# 02_Interfaces.net
KiCad netlist of a schematic drawn in Altium Designer
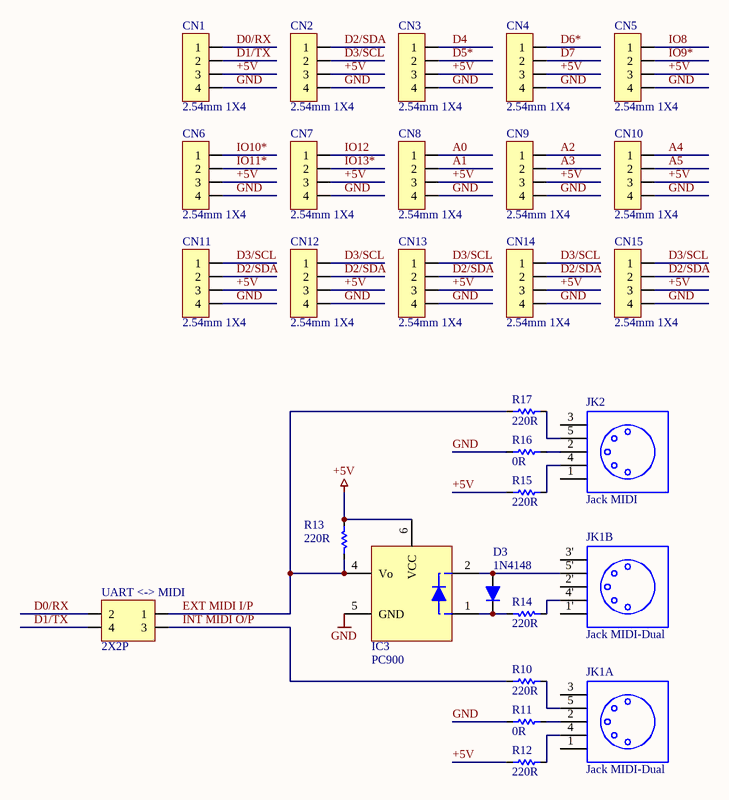
[diagram p0: 02.Interfaces.SchDoc]

(export (version "E")
  (design (tool "Eeschema 10.0.6"))
  (components
    (comp (ref "CN1")
      (value "2.54mm 1X4")
      (footprint "Grove-4P-180D")
      (libsource (lib "MainnoLab library") (part "Connector 1X4"))
    )
    (comp (ref "CN2")
      (value "2.54mm 1X4")
      (footprint "Grove-4P-180D")
      (libsource (lib "MainnoLab library") (part "Connector 1X4"))
    )
    (comp (ref "CN3")
      (value "2.54mm 1X4")
      (footprint "Grove-4P-180D")
      (libsource (lib "MainnoLab library") (part "Connector 1X4"))
    )
    (comp (ref "CN4")
      (value "2.54mm 1X4")
      (footprint "Grove-4P-180D")
      (libsource (lib "MainnoLab library") (part "Connector 1X4"))
    )
    (comp (ref "CN5")
      (value "2.54mm 1X4")
      (footprint "Grove-4P-180D")
      (libsource (lib "MainnoLab library") (part "Connector 1X4"))
    )
    (comp (ref "CN6")
      (value "2.54mm 1X4")
      (footprint "Grove-4P-180D")
      (libsource (lib "MainnoLab library") (part "Connector 1X4"))
    )
    (comp (ref "CN7")
      (value "2.54mm 1X4")
      (footprint "Grove-4P-180D")
      (libsource (lib "MainnoLab library") (part "Connector 1X4"))
    )
    (comp (ref "CN8")
      (value "2.54mm 1X4")
      (footprint "Grove-4P-180D")
      (libsource (lib "MainnoLab library") (part "Connector 1X4"))
    )
    (comp (ref "CN9")
      (value "2.54mm 1X4")
      (footprint "Grove-4P-180D")
      (libsource (lib "MainnoLab library") (part "Connector 1X4"))
    )
    (comp (ref "CN10")
      (value "2.54mm 1X4")
      (footprint "Grove-4P-180D")
      (libsource (lib "MainnoLab library") (part "Connector 1X4"))
    )
    (comp (ref "CN11")
      (value "2.54mm 1X4")
      (footprint "Grove-4P-180D")
      (libsource (lib "MainnoLab library") (part "Connector 1X4"))
    )
    (comp (ref "CN12")
      (value "2.54mm 1X4")
      (footprint "Grove-4P-180D")
      (libsource (lib "MainnoLab library") (part "Connector 1X4"))
    )
    (comp (ref "CN13")
      (value "2.54mm 1X4")
      (footprint "Grove-4P-180D")
      (libsource (lib "MainnoLab library") (part "Connector 1X4"))
    )
    (comp (ref "CN14")
      (value "2.54mm 1X4")
      (footprint "Grove-4P-180D")
      (libsource (lib "MainnoLab library") (part "Connector 1X4"))
    )
    (comp (ref "CN15")
      (value "2.54mm 1X4")
      (footprint "Grove-4P-180D")
      (libsource (lib "MainnoLab library") (part "Connector 1X4"))
    )
    (comp (ref "D3")
      (value "1N4148")
      (footprint "SOD-323")
      (libsource (lib "Jixuan's library") (part "Diode 1N4148"))
    )
    (comp (ref "IC3")
      (value "PC900")
      (footprint "DIP-6")
      (description "Sharp PC900 Optoisolator")
      (libsource (lib "Jixuan's library") (part "Optoisolator PC900"))
    )
    (comp (ref "JK1")
      (value "Jack MIDI-Dual")
      (footprint "HDC-052")
      (description "Dual MIDI Connector")
      (libsource (lib "Jixuan's library") (part "Jack MIDI-Dual"))
    )
    (comp (ref "JK2")
      (value "Jack MIDI")
      (footprint "HDC-052-01")
      (libsource (lib "MainnoLab library") (part "Jack MIDI"))
    )
    (comp (ref "R10")
      (value "220R")
      (footprint "R0603-ROUND")
      (libsource (lib "Jixuan's library") (part "Resistor"))
    )
    (comp (ref "R11")
      (value "0R")
      (footprint "R0603-ROUND")
      (libsource (lib "Jixuan's library") (part "Resistor"))
    )
    (comp (ref "R12")
      (value "220R")
      (footprint "R0603-ROUND")
      (libsource (lib "Jixuan's library") (part "Resistor"))
    )
    (comp (ref "R13")
      (value "220R")
      (footprint "R0603-ROUND")
      (libsource (lib "Jixuan's library") (part "Resistor"))
    )
    (comp (ref "R14")
      (value "220R")
      (footprint "R0603-ROUND")
      (libsource (lib "Jixuan's library") (part "Resistor"))
    )
    (comp (ref "R15")
      (value "220R")
      (footprint "R0603-ROUND")
      (libsource (lib "Jixuan's library") (part "Resistor"))
    )
    (comp (ref "R16")
      (value "0R")
      (footprint "R0603-ROUND")
      (libsource (lib "Jixuan's library") (part "Resistor"))
    )
    (comp (ref "R17")
      (value "220R")
      (footprint "R0603-ROUND")
      (libsource (lib "Jixuan's library") (part "Resistor"))
    )
    (comp (ref "UART <-> MIDI")
      (value "2X2P")
      (footprint "A2541WV0-2X2P")
      (libsource (lib "Jixuan's library") (part "Connector 2X2"))
    )
  )
  (nets
    (net (code "1") (name "+5V") (class "Default")
      (node (ref "CN1") (pin "3") (pinfunction "3_3") (pintype "passive"))
      (node (ref "CN10") (pin "3") (pinfunction "3_3") (pintype "passive"))
      (node (ref "CN11") (pin "3") (pinfunction "3_3") (pintype "passive"))
      (node (ref "CN12") (pin "3") (pinfunction "3_3") (pintype "passive"))
      (node (ref "CN13") (pin "3") (pinfunction "3_3") (pintype "passive"))
      (node (ref "CN14") (pin "3") (pinfunction "3_3") (pintype "passive"))
      (node (ref "CN15") (pin "3") (pinfunction "3_3") (pintype "passive"))
      (node (ref "CN2") (pin "3") (pinfunction "3_3") (pintype "passive"))
      (node (ref "CN3") (pin "3") (pinfunction "3_3") (pintype "passive"))
      (node (ref "CN4") (pin "3") (pinfunction "3_3") (pintype "passive"))
      (node (ref "CN5") (pin "3") (pinfunction "3_3") (pintype "passive"))
      (node (ref "CN6") (pin "3") (pinfunction "3_3") (pintype "passive"))
      (node (ref "CN7") (pin "3") (pinfunction "3_3") (pintype "passive"))
      (node (ref "CN8") (pin "3") (pinfunction "3_3") (pintype "passive"))
      (node (ref "CN9") (pin "3") (pinfunction "3_3") (pintype "passive"))
      (node (ref "IC3") (pin "6") (pinfunction "VCC_6") (pintype "passive"))
      (node (ref "R12") (pin "1") (pinfunction "1_1") (pintype "passive"))
      (node (ref "R13") (pin "2") (pinfunction "2_2") (pintype "passive"))
      (node (ref "R15") (pin "1") (pinfunction "1_1") (pintype "passive"))
    )
    (net (code "2") (name "/A0") (class "Default")
      (node (ref "CN8") (pin "1") (pinfunction "1_1") (pintype "passive"))
    )
    (net (code "3") (name "/A1") (class "Default")
      (node (ref "CN8") (pin "2") (pinfunction "2_2") (pintype "passive"))
    )
    (net (code "4") (name "/A2") (class "Default")
      (node (ref "CN9") (pin "1") (pinfunction "1_1") (pintype "passive"))
    )
    (net (code "5") (name "/A3") (class "Default")
      (node (ref "CN9") (pin "2") (pinfunction "2_2") (pintype "passive"))
    )
    (net (code "6") (name "/A4") (class "Default")
      (node (ref "CN10") (pin "1") (pinfunction "1_1") (pintype "passive"))
    )
    (net (code "7") (name "/A5") (class "Default")
      (node (ref "CN10") (pin "2") (pinfunction "2_2") (pintype "passive"))
    )
    (net (code "8") (name "/D0{slash}RX") (class "Default")
      (node (ref "CN1") (pin "1") (pinfunction "1_1") (pintype "passive"))
      (node (ref "UART <-> MIDI") (pin "2") (pinfunction "2_2") (pintype "passive"))
    )
    (net (code "9") (name "/D1{slash}TX") (class "Default")
      (node (ref "CN1") (pin "2") (pinfunction "2_2") (pintype "passive"))
      (node (ref "UART <-> MIDI") (pin "4") (pinfunction "4_4") (pintype "passive"))
    )
    (net (code "10") (name "/D2{slash}SDA") (class "Default")
      (node (ref "CN11") (pin "2") (pinfunction "2_2") (pintype "passive"))
      (node (ref "CN12") (pin "2") (pinfunction "2_2") (pintype "passive"))
      (node (ref "CN13") (pin "2") (pinfunction "2_2") (pintype "passive"))
      (node (ref "CN14") (pin "2") (pinfunction "2_2") (pintype "passive"))
      (node (ref "CN15") (pin "2") (pinfunction "2_2") (pintype "passive"))
      (node (ref "CN2") (pin "1") (pinfunction "1_1") (pintype "passive"))
    )
    (net (code "11") (name "/D3{slash}SCL") (class "Default")
      (node (ref "CN11") (pin "1") (pinfunction "1_1") (pintype "passive"))
      (node (ref "CN12") (pin "1") (pinfunction "1_1") (pintype "passive"))
      (node (ref "CN13") (pin "1") (pinfunction "1_1") (pintype "passive"))
      (node (ref "CN14") (pin "1") (pinfunction "1_1") (pintype "passive"))
      (node (ref "CN15") (pin "1") (pinfunction "1_1") (pintype "passive"))
      (node (ref "CN2") (pin "2") (pinfunction "2_2") (pintype "passive"))
    )
    (net (code "12") (name "/D4") (class "Default")
      (node (ref "CN3") (pin "1") (pinfunction "1_1") (pintype "passive"))
    )
    (net (code "13") (name "/D5*") (class "Default")
      (node (ref "CN3") (pin "2") (pinfunction "2_2") (pintype "passive"))
    )
    (net (code "14") (name "/D6*") (class "Default")
      (node (ref "CN4") (pin "1") (pinfunction "1_1") (pintype "passive"))
    )
    (net (code "15") (name "/D7") (class "Default")
      (node (ref "CN4") (pin "2") (pinfunction "2_2") (pintype "passive"))
    )
    (net (code "16") (name "/EXT MIDI I{slash}P") (class "Default")
      (node (ref "IC3") (pin "4") (pinfunction "Vo_4") (pintype "passive"))
      (node (ref "R13") (pin "1") (pinfunction "1_1") (pintype "passive"))
      (node (ref "R17") (pin "1") (pinfunction "1_1") (pintype "passive"))
      (node (ref "UART <-> MIDI") (pin "1") (pinfunction "1_1") (pintype "passive"))
    )
    (net (code "17") (name "/INT MIDI O{slash}P") (class "Default")
      (node (ref "R10") (pin "1") (pinfunction "1_1") (pintype "passive"))
      (node (ref "UART <-> MIDI") (pin "3") (pinfunction "3_3") (pintype "passive"))
    )
    (net (code "18") (name "/IO8") (class "Default")
      (node (ref "CN5") (pin "1") (pinfunction "1_1") (pintype "passive"))
    )
    (net (code "19") (name "/IO9*") (class "Default")
      (node (ref "CN5") (pin "2") (pinfunction "2_2") (pintype "passive"))
    )
    (net (code "20") (name "/IO10*") (class "Default")
      (node (ref "CN6") (pin "1") (pinfunction "1_1") (pintype "passive"))
    )
    (net (code "21") (name "/IO11*") (class "Default")
      (node (ref "CN6") (pin "2") (pinfunction "2_2") (pintype "passive"))
    )
    (net (code "22") (name "/IO12") (class "Default")
      (node (ref "CN7") (pin "1") (pinfunction "1_1") (pintype "passive"))
    )
    (net (code "23") (name "/IO13*") (class "Default")
      (node (ref "CN7") (pin "2") (pinfunction "2_2") (pintype "passive"))
    )
    (net (code "24") (name "GND") (class "Default")
      (node (ref "CN1") (pin "4") (pinfunction "4_4") (pintype "passive"))
      (node (ref "CN10") (pin "4") (pinfunction "4_4") (pintype "passive"))
      (node (ref "CN11") (pin "4") (pinfunction "4_4") (pintype "passive"))
      (node (ref "CN12") (pin "4") (pinfunction "4_4") (pintype "passive"))
      (node (ref "CN13") (pin "4") (pinfunction "4_4") (pintype "passive"))
      (node (ref "CN14") (pin "4") (pinfunction "4_4") (pintype "passive"))
      (node (ref "CN15") (pin "4") (pinfunction "4_4") (pintype "passive"))
      (node (ref "CN2") (pin "4") (pinfunction "4_4") (pintype "passive"))
      (node (ref "CN3") (pin "4") (pinfunction "4_4") (pintype "passive"))
      (node (ref "CN4") (pin "4") (pinfunction "4_4") (pintype "passive"))
      (node (ref "CN5") (pin "4") (pinfunction "4_4") (pintype "passive"))
      (node (ref "CN6") (pin "4") (pinfunction "4_4") (pintype "passive"))
      (node (ref "CN7") (pin "4") (pinfunction "4_4") (pintype "passive"))
      (node (ref "CN8") (pin "4") (pinfunction "4_4") (pintype "passive"))
      (node (ref "CN9") (pin "4") (pinfunction "4_4") (pintype "passive"))
      (node (ref "IC3") (pin "5") (pinfunction "GND_5") (pintype "passive"))
      (node (ref "R11") (pin "1") (pinfunction "1_1") (pintype "passive"))
      (node (ref "R16") (pin "1") (pinfunction "1_1") (pintype "passive"))
    )
    (net (code "25") (name "Net-(D3-Pad1)") (class "Default")
      (node (ref "D3") (pin "1") (pinfunction "1_1") (pintype "passive"))
      (node (ref "IC3") (pin "2") (pinfunction "2_2") (pintype "passive"))
      (node (ref "JK1") (pin "5'") (pinfunction "5'_5'") (pintype "passive"))
    )
    (net (code "26") (name "Net-(D3-Pad2)") (class "Default")
      (node (ref "D3") (pin "2") (pinfunction "2_2") (pintype "passive"))
      (node (ref "IC3") (pin "1") (pinfunction "1_1") (pintype "passive"))
      (node (ref "R14") (pin "2") (pinfunction "2_2") (pintype "passive"))
    )
    (net (code "27") (name "Net-(JK1-Pad2)") (class "Default")
      (node (ref "JK1") (pin "2") (pinfunction "2_2") (pintype "passive"))
      (node (ref "R11") (pin "2") (pinfunction "2_2") (pintype "passive"))
    )
    (net (code "28") (name "Net-(JK1-Pad4')") (class "Default")
      (node (ref "JK1") (pin "4'") (pinfunction "4'_4'") (pintype "passive"))
      (node (ref "R14") (pin "1") (pinfunction "1_1") (pintype "passive"))
    )
    (net (code "29") (name "Net-(JK1-Pad4)") (class "Default")
      (node (ref "JK1") (pin "4") (pinfunction "4_4") (pintype "passive"))
      (node (ref "R12") (pin "2") (pinfunction "2_2") (pintype "passive"))
    )
    (net (code "30") (name "Net-(JK1-Pad5)") (class "Default")
      (node (ref "JK1") (pin "5") (pinfunction "5_5") (pintype "passive"))
      (node (ref "R10") (pin "2") (pinfunction "2_2") (pintype "passive"))
    )
    (net (code "31") (name "Net-(JK2-Pad2)") (class "Default")
      (node (ref "JK2") (pin "2") (pinfunction "2_2") (pintype "passive"))
      (node (ref "R16") (pin "2") (pinfunction "2_2") (pintype "passive"))
    )
    (net (code "32") (name "Net-(JK2-Pad4)") (class "Default")
      (node (ref "JK2") (pin "4") (pinfunction "4_4") (pintype "passive"))
      (node (ref "R15") (pin "2") (pinfunction "2_2") (pintype "passive"))
    )
    (net (code "33") (name "Net-(JK2-Pad5)") (class "Default")
      (node (ref "JK2") (pin "5") (pinfunction "5_5") (pintype "passive"))
      (node (ref "R17") (pin "2") (pinfunction "2_2") (pintype "passive"))
    )
    (net (code "34") (name "unconnected-(JK1-Pad1')") (class "Default")
      (node (ref "JK1") (pin "1'") (pinfunction "1'_1'") (pintype "passive"))
    )
    (net (code "35") (name "unconnected-(JK1-Pad1)") (class "Default")
      (node (ref "JK1") (pin "1") (pinfunction "1_1") (pintype "passive"))
    )
    (net (code "36") (name "unconnected-(JK1-Pad3')") (class "Default")
      (node (ref "JK1") (pin "3'") (pinfunction "3'_3'") (pintype "passive"))
    )
    (net (code "37") (name "unconnected-(JK1-Pad3)") (class "Default")
      (node (ref "JK1") (pin "3") (pinfunction "3_3") (pintype "passive"))
    )
    (net (code "38") (name "unconnected-(JK1B-2-Pad2')") (class "Default")
      (node (ref "JK1") (pin "2'") (pinfunction "2_2'") (pintype "passive"))
    )
    (net (code "39") (name "unconnected-(JK2-Pad1)") (class "Default")
      (node (ref "JK2") (pin "1") (pinfunction "1_1") (pintype "passive"))
    )
    (net (code "40") (name "unconnected-(JK2-Pad3)") (class "Default")
      (node (ref "JK2") (pin "3") (pinfunction "3_3") (pintype "passive"))
    )
  )
)
